# Power.net
KiCad netlist of a schematic drawn in Altium Designer
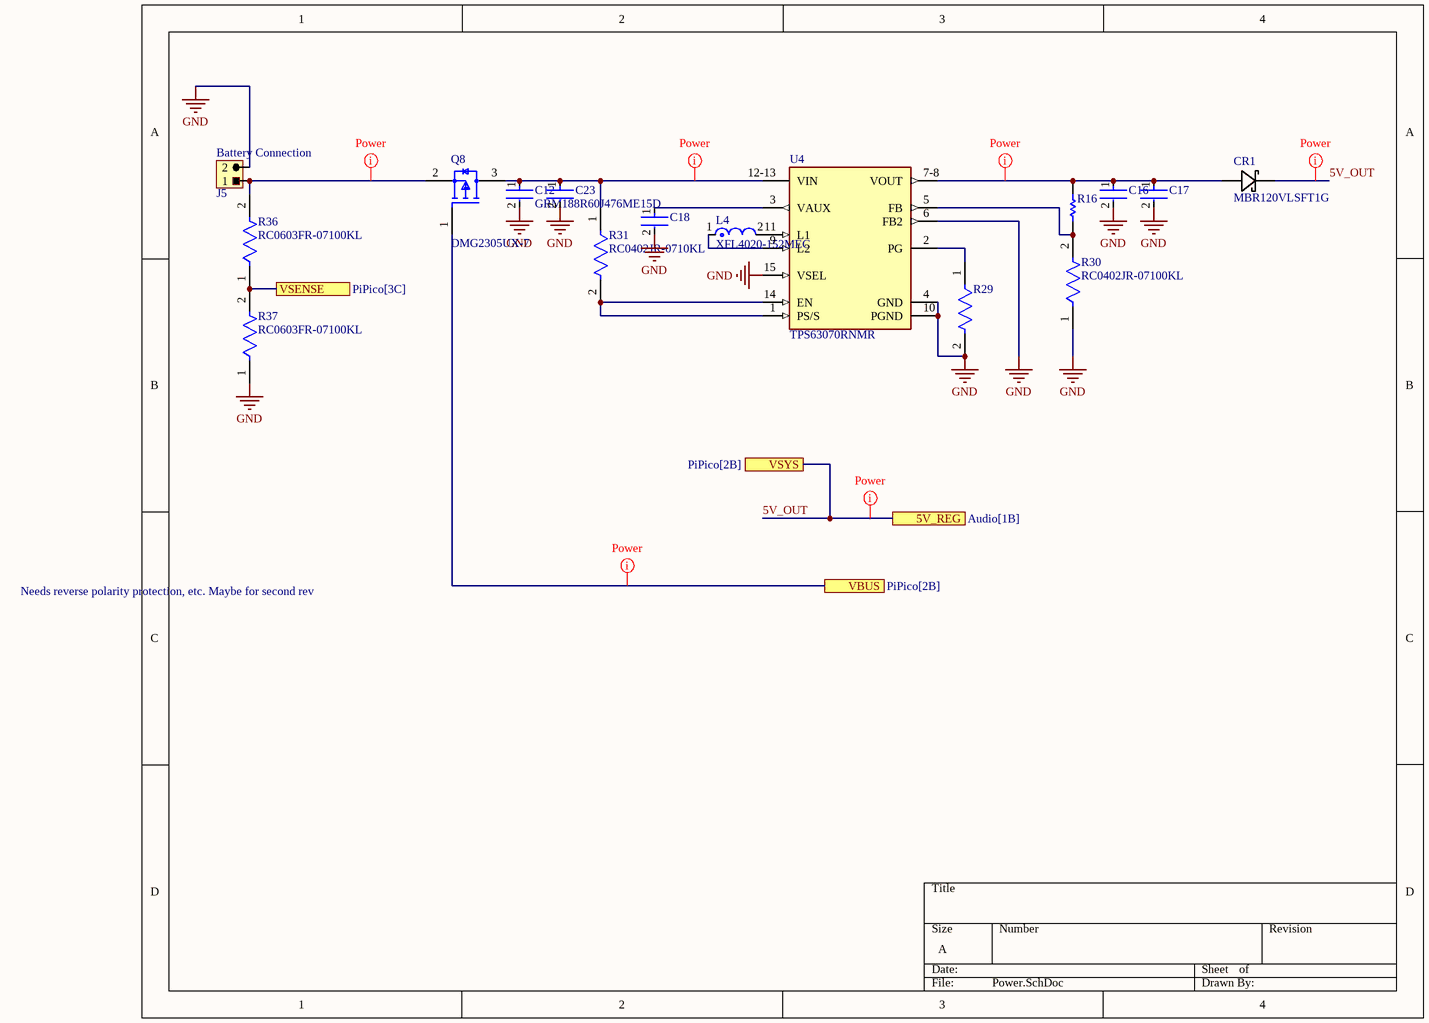
[diagram p0: Power.SchDoc]

(export (version "E")
  (design (tool "Eeschema 10.0.6"))
  (components
    (comp (ref "C12")
      (value "GRM188R60J476ME15D")
      (footprint "FP-GRM188-0_2-IPC_B")
      (description "Chip Multilayer Ceramic Capacitors for General Purpose, 0603, 47uF, X5R, 15%, 20%, 6.3V")
      (fields (field (name "TOLERANCE") "20%"))
      (libsource (lib "Altium Content Vault") (part "11868f565c42a9108669ba33697ecf6"))
    )
    (comp (ref "C16")
      (value "C0603C106M9PACTU")
      (footprint "FP-C0603C106M9PACTU-MFG")
      (description "CAP CER 10UF 6.3V X5R 0603")
      (fields
        (field (name "MANUFACTURER") "Kemet")
        (field (name "OCTOPART") "https://octopart.com/c0603c106m9pactu-kemet-8375727")
      )
      (libsource (lib "Altium Content Vault") (part "b4654b650e69147ec39a6b967a45e02"))
    )
    (comp (ref "C17")
      (value "GRM188R60J476ME15D")
      (footprint "FP-GRM188-0_2-IPC_B")
      (description "Chip Multilayer Ceramic Capacitors for General Purpose, 0603, 47uF, X5R, 15%, 20%, 6.3V")
      (fields (field (name "TOLERANCE") "20%"))
      (libsource (lib "Altium Content Vault") (part "11868f565c42a9108669ba33697ecf6"))
    )
    (comp (ref "C18")
      (value "C0402C104K8PACTU")
      (footprint "FP-C0402-BB-MFG")
      (description "CAP CER 0.1UF 10V X5R 0402")
      (fields (field (name "MANUFACTURER") "Kemet") (field (name "TOLERANCE") "0.1"))
      (libsource (lib "Altium Content Vault") (part "b4654b650e69147ec39a6b967a45e02"))
    )
    (comp (ref "C23")
      (value "C0603C106M9PACTU")
      (footprint "FP-C0603C106M9PACTU-MFG")
      (description "CAP CER 10UF 6.3V X5R 0603")
      (fields
        (field (name "MANUFACTURER") "Kemet")
        (field (name "OCTOPART") "https://octopart.com/c0603c106m9pactu-kemet-8375727")
      )
      (libsource (lib "Altium Content Vault") (part "b4654b650e69147ec39a6b967a45e02"))
    )
    (comp (ref "CR1")
      (value "MBR120VLSFT1G")
      (footprint "SDO_SOD-123FL_ONS")
      (description "No Description Available")
      (libsource (lib "ECE299_PCB") (part "MBR120VLSFT1G"))
    )
    (comp (ref "J5")
      (value "Battery Connection")
      (footprint "2-pin Header (Generic)")
      (libsource (lib "ECE299_PCB") (part "2-PIN HEADER"))
    )
    (comp (ref "L4")
      (value "XFL4020-152MEC")
      (footprint "FP-XFL4020-MFG")
      (fields (field (name "TOLERANCE") "20%"))
      (libsource (lib "Altium Content Vault") (part "4cc4b267dca4c8e51f7102f422741d8"))
    )
    (comp (ref "Q8")
      (value "DMG2305UX-7")
      (footprint "FP-SOT23-IPC_B")
      (description "MOSFET P-CH 20V 4.2A SOT23")
      (libsource (lib "Altium Content Vault") (part "87831b450059b469d4a68f5364f4496"))
    )
    (comp (ref "R16")
      (value "RC0402FR-07523KL")
      (footprint "RESC1005X40X25NL05T10")
      (fields (field (name "MANUFACTURER") "Yageo / Phycomp"))
      (libsource (lib "Altium Content Vault") (part "RES"))
    )
    (comp (ref "R29")
      (value "RC0402JR-07100KL")
      (footprint "FP-RC0402-0_4-IPC_A")
      (description "RES 100K OHM 5% 1/16W 0402")
      (fields (field (name "TOLERANCE") "5%"))
      (libsource (lib "Altium Content Vault") (part "1029c3af85768c4190bb7ad29bc67b5"))
    )
    (comp (ref "R30")
      (value "RC0402JR-07100KL")
      (footprint "FP-RC0402-0_4-IPC_A")
      (description "RES 100K OHM 5% 1/16W 0402")
      (fields (field (name "TOLERANCE") "5%"))
      (libsource (lib "Altium Content Vault") (part "1029c3af85768c4190bb7ad29bc67b5"))
    )
    (comp (ref "R31")
      (value "RC0402JR-0710KL")
      (footprint "RC0402N_YAG")
      (description "RES 10K OHM 5% 1/16W 0402")
      (fields (field (name "TOLERANCE") "5%"))
      (libsource (lib "ECE299_PCB") (part "CMP-2002-07915-3"))
    )
    (comp (ref "R36")
      (value "RC0603FR-07100KL")
      (footprint "FP-RC0603-0_55-MFG")
      (description "RES SMD 100K OHM 1% 1/10W 0603")
      (fields (field (name "TOLERANCE") "1%"))
      (libsource (lib "Altium Content Vault") (part "1029c3af85768c4190bb7ad29bc67b5"))
    )
    (comp (ref "R37")
      (value "RC0603FR-07100KL")
      (footprint "FP-RC0603-0_55-MFG")
      (description "RES SMD 100K OHM 1% 1/10W 0603")
      (fields (field (name "TOLERANCE") "1%"))
      (libsource (lib "Altium Content Vault") (part "1029c3af85768c4190bb7ad29bc67b5"))
    )
    (comp (ref "U4")
      (value "TPS63070RNMR")
      (footprint "FP-RNM0015A-MFG")
      (description "IC REG BCK BST ADJ 3.6A 15VQFN")
      (libsource (lib "Altium Content Vault") (part "a4d5b1e6901c8533e317c4aea8f1b15"))
    )
  )
  (nets
    (net (code "1") (name "/5V_OUT") (class "Default")
      (node (ref "CR1") (pin "1") (pinfunction "1_1") (pintype "passive"))
    )
    (net (code "2") (name "/VBUS") (class "Default")
      (node (ref "Q8") (pin "1") (pinfunction "GATE_1") (pintype "passive"))
    )
    (net (code "3") (name "/VSENSE") (class "Default")
      (node (ref "R36") (pin "1") (pinfunction "1_1") (pintype "passive"))
      (node (ref "R37") (pin "2") (pinfunction "2_2") (pintype "passive"))
    )
    (net (code "4") (name "GND") (class "Default")
      (node (ref "C12") (pin "2") (pinfunction "2_2") (pintype "passive"))
      (node (ref "C16") (pin "2") (pinfunction "2_2") (pintype "passive"))
      (node (ref "C17") (pin "2") (pinfunction "2_2") (pintype "passive"))
      (node (ref "C18") (pin "2") (pinfunction "2_2") (pintype "passive"))
      (node (ref "C23") (pin "2") (pinfunction "2_2") (pintype "passive"))
      (node (ref "J5") (pin "2") (pinfunction "2_2") (pintype "passive"))
      (node (ref "R29") (pin "2") (pinfunction "2_2") (pintype "passive"))
      (node (ref "R30") (pin "1") (pinfunction "1_1") (pintype "passive"))
      (node (ref "R37") (pin "1") (pinfunction "1_1") (pintype "passive"))
      (node (ref "U4") (pin "10") (pinfunction "PGND_10") (pintype "power_in"))
      (node (ref "U4") (pin "15") (pinfunction "VSEL_15") (pintype "input"))
      (node (ref "U4") (pin "4") (pinfunction "GND_4") (pintype "power_in"))
      (node (ref "U4") (pin "6") (pinfunction "FB2_6") (pintype "output"))
    )
    (net (code "5") (name "Net-(Q8-DRAIN)") (class "Default")
      (node (ref "C12") (pin "1") (pinfunction "1_1") (pintype "passive"))
      (node (ref "C23") (pin "1") (pinfunction "1_1") (pintype "passive"))
      (node (ref "Q8") (pin "3") (pinfunction "DRAIN_3") (pintype "passive"))
      (node (ref "R31") (pin "1") (pinfunction "1_1") (pintype "passive"))
      (node (ref "U4") (pin "12-13") (pinfunction "VIN_12-13") (pintype "power_in"))
    )
    (net (code "6") (name "Net-(Q8-SOURCE)") (class "Default")
      (node (ref "J5") (pin "1") (pinfunction "1_1") (pintype "passive"))
      (node (ref "Q8") (pin "2") (pinfunction "SOURCE_2") (pintype "passive"))
      (node (ref "R36") (pin "2") (pinfunction "2_2") (pintype "passive"))
    )
    (net (code "7") (name "Net-(U4-EN)") (class "Default")
      (node (ref "R31") (pin "2") (pinfunction "2_2") (pintype "passive"))
      (node (ref "U4") (pin "1") (pinfunction "PS/S_1") (pintype "input"))
      (node (ref "U4") (pin "14") (pinfunction "EN_14") (pintype "input"))
    )
    (net (code "8") (name "Net-(U4-FB)") (class "Default")
      (node (ref "R16") (pin "1") (pinfunction "1_1") (pintype "passive"))
      (node (ref "R30") (pin "2") (pinfunction "2_2") (pintype "passive"))
      (node (ref "U4") (pin "5") (pinfunction "FB_5") (pintype "output"))
    )
    (net (code "9") (name "Net-(U4-L1)") (class "Default")
      (node (ref "L4") (pin "2") (pinfunction "2_2") (pintype "passive"))
      (node (ref "U4") (pin "11") (pinfunction "L1_11") (pintype "input"))
    )
    (net (code "10") (name "Net-(U4-L2)") (class "Default")
      (node (ref "L4") (pin "1") (pinfunction "1_1") (pintype "passive"))
      (node (ref "U4") (pin "9") (pinfunction "L2_9") (pintype "input"))
    )
    (net (code "11") (name "Net-(U4-PG)") (class "Default")
      (node (ref "R29") (pin "1") (pinfunction "1_1") (pintype "passive"))
      (node (ref "U4") (pin "2") (pinfunction "PG_2") (pintype "open_collector"))
    )
    (net (code "12") (name "Net-(U4-VAUX)") (class "Default")
      (node (ref "C18") (pin "1") (pinfunction "1_1") (pintype "passive"))
      (node (ref "U4") (pin "3") (pinfunction "VAUX_3") (pintype "output"))
    )
    (net (code "13") (name "Net-(U4-VOUT)") (class "Default")
      (node (ref "C16") (pin "1") (pinfunction "1_1") (pintype "passive"))
      (node (ref "C17") (pin "1") (pinfunction "1_1") (pintype "passive"))
      (node (ref "CR1") (pin "2") (pinfunction "2_2") (pintype "passive"))
      (node (ref "R16") (pin "2") (pinfunction "2_2") (pintype "passive"))
      (node (ref "U4") (pin "7-8") (pinfunction "VOUT_7-8") (pintype "output"))
    )
  )
)
